# 2V_REG.net
KiCad netlist of a schematic drawn in Altium Designer
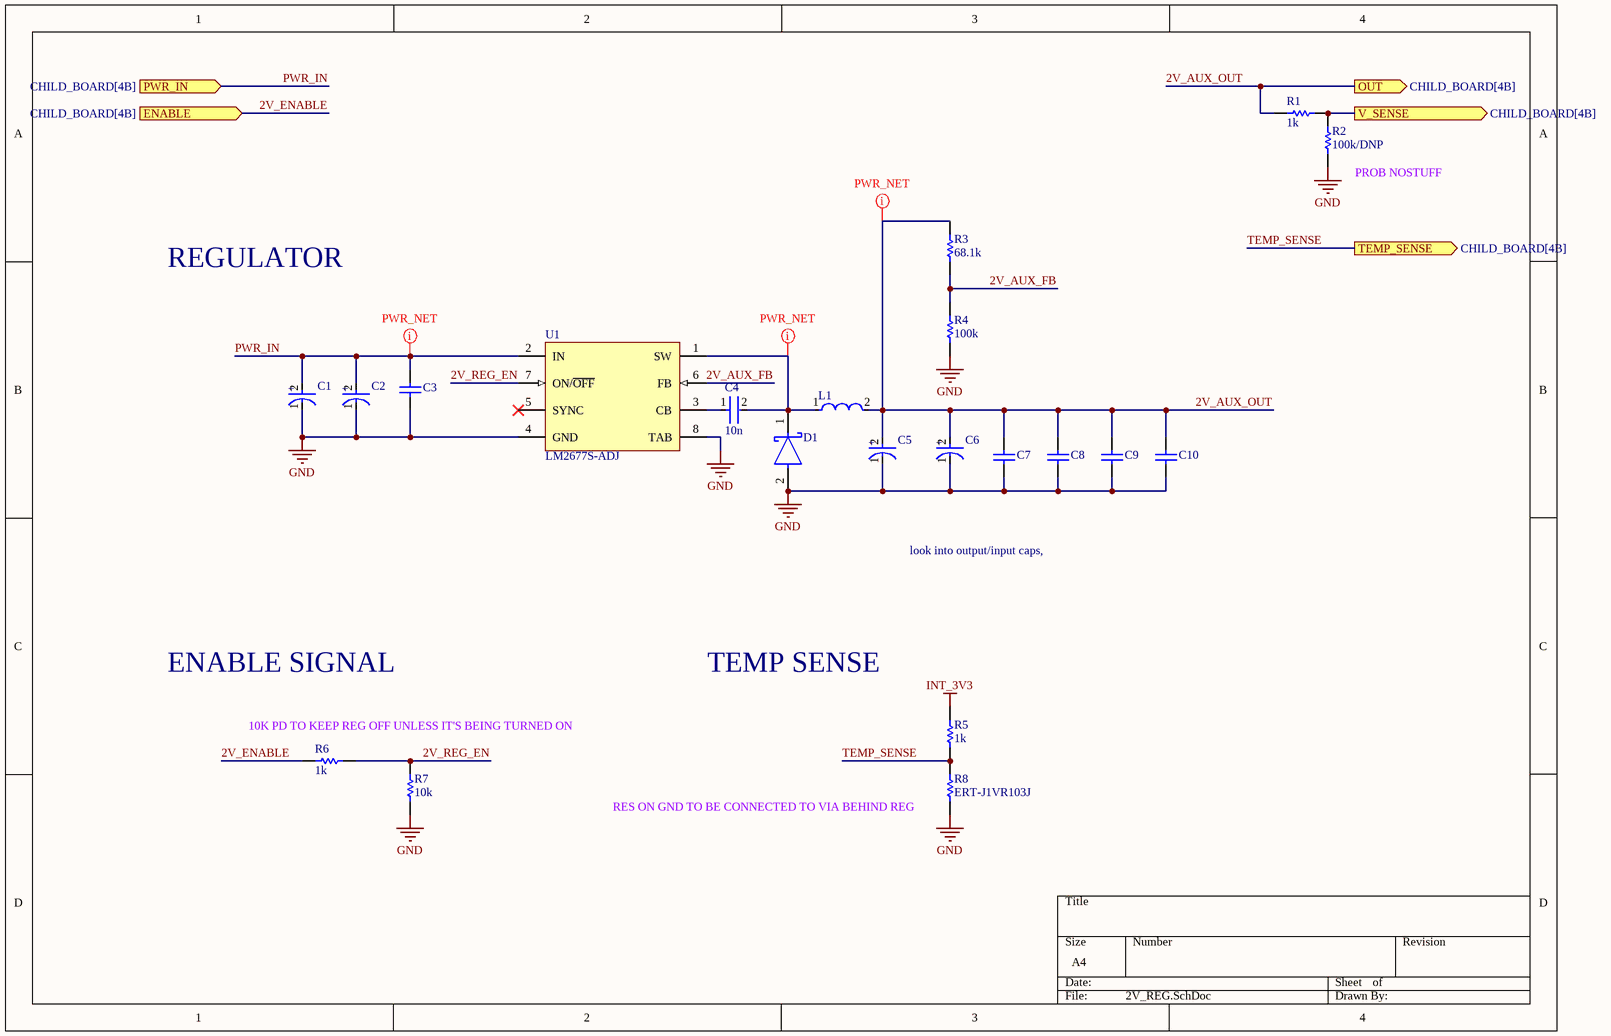
[diagram p0: 2V_REG.SchDoc]

(export (version "E")
  (design (tool "Eeschema 10.0.6"))
  (components
    (comp (ref "C1")
      (value "EEHZA1V680XP")
      (footprint "FP-EEH-D8-MFG")
      (description "Conductive Polymer Hybrid Aluminum Electrolytic Capacitors 68uF ±20% 35V RADIAL SMT 6.3x7.7mm")
      (fields (field (name "VOLTAGE") "35V") (field (name "TOLERANCE") "20%"))
      (libsource (lib "Altium Content Vault") (part "a00bbbee19879c290e62620ae7e47b1"))
    )
    (comp (ref "C2")
      (value "EEHZA1V680XP")
      (footprint "FP-EEH-D8-MFG")
      (description "Conductive Polymer Hybrid Aluminum Electrolytic Capacitors 68uF ±20% 35V RADIAL SMT 6.3x7.7mm")
      (fields (field (name "VOLTAGE") "35V") (field (name "TOLERANCE") "20%"))
      (libsource (lib "Altium Content Vault") (part "a00bbbee19879c290e62620ae7e47b1"))
    )
    (comp (ref "C3")
      (value "CAP 470nF 50V 1812(4532)")
      (footprint "CAPC1812(4532)125_M")
      (description "CAP 470nF 50V ±10% 1812 (4532 Metric) Thickness 1.25mm SMD")
      (fields (field (name "TOLERANCE") "Â±10%"))
      (libsource (lib "Altium Content Vault") (part "CAP"))
    )
    (comp (ref "C4")
      (value "10n")
      (footprint "FP-0402-L_1_0_0_05-W_0_5-IPC_A")
      (description "LARGE PADS, 0402 CAP, CHANGE COMMENT TO MATCH REAL P/N")
      (libsource (lib "Space Concordia") (part "b4654b650e69147ec39a6b967a45e02"))
    )
    (comp (ref "C5")
      (value "16SVPC120M")
      (footprint "FP-OS-CON-SMT-E7-MFG")
      (description "Conductive Polymer Aluminum Solid Capacitors (OS-CON) 120uF ±20% 16V RADIAL SMT 8x6.9mm")
      (fields (field (name "VOLTAGE") "16V") (field (name "TOLERANCE") "20%"))
      (libsource (lib "Altium Content Vault") (part "cf48714ba7e38822c1575c7ec0b6d1f"))
    )
    (comp (ref "C6")
      (value "16SVPC120M")
      (footprint "FP-OS-CON-SMT-E7-MFG")
      (description "Conductive Polymer Aluminum Solid Capacitors (OS-CON) 120uF ±20% 16V RADIAL SMT 8x6.9mm")
      (fields (field (name "VOLTAGE") "16V") (field (name "TOLERANCE") "20%"))
      (libsource (lib "Altium Content Vault") (part "cf48714ba7e38822c1575c7ec0b6d1f"))
    )
    (comp (ref "C7")
      (value "CAP 470nF 50V 1812(4532)")
      (footprint "CAPC1812(4532)125_M")
      (description "CAP 470nF 50V ±10% 1812 (4532 Metric) Thickness 1.25mm SMD")
      (fields (field (name "TOLERANCE") "Â±10%"))
      (libsource (lib "Altium Content Vault") (part "CAP"))
    )
    (comp (ref "C8")
      (value "CAP 470nF 50V 1812(4532)")
      (footprint "CAPC1812(4532)125_M")
      (description "CAP 470nF 50V ±10% 1812 (4532 Metric) Thickness 1.25mm SMD")
      (fields (field (name "TOLERANCE") "Â±10%"))
      (libsource (lib "Altium Content Vault") (part "CAP"))
    )
    (comp (ref "C9")
      (value "CAP 470nF 50V 1812(4532)")
      (footprint "CAPC1812(4532)125_M")
      (description "CAP 470nF 50V ±10% 1812 (4532 Metric) Thickness 1.25mm SMD")
      (fields (field (name "TOLERANCE") "Â±10%"))
      (libsource (lib "Altium Content Vault") (part "CAP"))
    )
    (comp (ref "C10")
      (value "CAP 470nF 50V 1812(4532)")
      (footprint "CAPC1812(4532)125_M")
      (description "CAP 470nF 50V ±10% 1812 (4532 Metric) Thickness 1.25mm SMD")
      (fields (field (name "TOLERANCE") "Â±10%"))
      (libsource (lib "Altium Content Vault") (part "CAP"))
    )
    (comp (ref "D1")
      (value "B540C-13-F")
      (footprint "FP-SMC-MFG")
      (description "DIODE SCHOTTKY 40V 5A SMC")
      (fields
        (field (name "OCTOPART") "https://octopart.com/b540c-13-f-diodes+inc.-325873")
        (field (name "MANUFACTURER") "Diodes Inc.")
      )
      (libsource (lib "Altium Content Vault") (part "1d6ec82d83fb6aee721767c19dac4b9"))
    )
    (comp (ref "L1")
      (value "SRR1260-150M")
      (footprint "FP-SRR1260-MFG")
      (description "FIXED IND 15UH 5A 27 MOHM SMD")
      (fields (field (name "TOLERANCE") "20%"))
      (libsource (lib "Altium Content Vault") (part "725321dda6339637d4d059423bc1c3c"))
    )
    (comp (ref "R1")
      (value "1k")
      (footprint "R0603B")
      (description "Resistor")
      (libsource (lib "Space Concordia") (part "Resistor"))
    )
    (comp (ref "R2")
      (value "100k/DNP")
      (footprint "R0603B")
      (description "Resistor")
      (libsource (lib "Space Concordia") (part "Resistor"))
    )
    (comp (ref "R3")
      (value "68.1k")
      (footprint "R0603B")
      (description "Resistor")
      (libsource (lib "Space Concordia") (part "Resistor"))
    )
    (comp (ref "R4")
      (value "100k")
      (footprint "R0603B")
      (description "Resistor")
      (libsource (lib "Space Concordia") (part "Resistor"))
    )
    (comp (ref "R5")
      (value "1k")
      (footprint "R0603B")
      (description "Resistor")
      (libsource (lib "Space Concordia") (part "Resistor"))
    )
    (comp (ref "R6")
      (value "1k")
      (footprint "R0603B")
      (description "Resistor")
      (libsource (lib "Space Concordia") (part "Resistor"))
    )
    (comp (ref "R7")
      (value "10k")
      (footprint "R0603B")
      (description "Resistor")
      (libsource (lib "Space Concordia") (part "Resistor"))
    )
    (comp (ref "R8")
      (value "ERT-J1VR103J")
      (footprint "RESC1608X90X30ML15T20")
      (fields (field (name "MANUFACTURER") "Panasonic"))
      (libsource (lib "Altium Content Vault") (part "RES"))
    )
    (comp (ref "U1")
      (value "LM2677S-ADJ")
      (footprint "KTW0007B_M")
      (description "SIMPLE SWITCHER® High Efficiency 5A Step-Down Voltage Regulator with Sync, 7-pin TO-263")
      (fields (field (name "MANUFACTURER") "Texas Instruments"))
      (libsource (lib "Altium Content Vault") (part "PM-REG-LM2670S-12"))
    )
  )
  (nets
    (net (code "1") (name "/2V_AUX_FB") (class "Default")
      (node (ref "R3") (pin "2") (pinfunction "2_2") (pintype "passive"))
      (node (ref "R4") (pin "1") (pinfunction "1_1") (pintype "passive"))
      (node (ref "U1") (pin "6") (pinfunction "FB_6") (pintype "input"))
    )
    (net (code "2") (name "/2V_AUX_OUT") (class "Default")
      (node (ref "C10") (pin "2") (pinfunction "2_2") (pintype "passive"))
      (node (ref "C5") (pin "2") (pinfunction "A_2") (pintype "passive"))
      (node (ref "C6") (pin "2") (pinfunction "A_2") (pintype "passive"))
      (node (ref "C7") (pin "2") (pinfunction "2_2") (pintype "passive"))
      (node (ref "C8") (pin "2") (pinfunction "2_2") (pintype "passive"))
      (node (ref "C9") (pin "2") (pinfunction "2_2") (pintype "passive"))
      (node (ref "L1") (pin "2") (pinfunction "2_2") (pintype "passive"))
      (node (ref "R1") (pin "1") (pinfunction "1_1") (pintype "passive"))
      (node (ref "R3") (pin "1") (pinfunction "1_1") (pintype "passive"))
    )
    (net (code "3") (name "/2V_ENABLE") (class "Default")
      (node (ref "R6") (pin "1") (pinfunction "1_1") (pintype "passive"))
    )
    (net (code "4") (name "/2V_REG_EN") (class "Default")
      (node (ref "R6") (pin "2") (pinfunction "2_2") (pintype "passive"))
      (node (ref "R7") (pin "1") (pinfunction "1_1") (pintype "passive"))
      (node (ref "U1") (pin "7") (pinfunction "ON/~{OFF}_7") (pintype "input"))
    )
    (net (code "5") (name "/PWR_IN") (class "Default")
      (node (ref "C1") (pin "2") (pinfunction "A_2") (pintype "passive"))
      (node (ref "C2") (pin "2") (pinfunction "A_2") (pintype "passive"))
      (node (ref "C3") (pin "2") (pinfunction "2_2") (pintype "passive"))
      (node (ref "U1") (pin "2") (pinfunction "IN_2") (pintype "power_in"))
    )
    (net (code "6") (name "/TEMP_SENSE") (class "Default")
      (node (ref "R5") (pin "1") (pinfunction "1_1") (pintype "passive"))
      (node (ref "R8") (pin "2") (pinfunction "2_2") (pintype "passive"))
    )
    (net (code "7") (name "/V_SENSE") (class "Default")
      (node (ref "R1") (pin "2") (pinfunction "2_2") (pintype "passive"))
      (node (ref "R2") (pin "1") (pinfunction "1_1") (pintype "passive"))
    )
    (net (code "8") (name "GND") (class "Default")
      (node (ref "C1") (pin "1") (pinfunction "C_1") (pintype "passive"))
      (node (ref "C10") (pin "1") (pinfunction "1_1") (pintype "passive"))
      (node (ref "C2") (pin "1") (pinfunction "C_1") (pintype "passive"))
      (node (ref "C3") (pin "1") (pinfunction "1_1") (pintype "passive"))
      (node (ref "C5") (pin "1") (pinfunction "C_1") (pintype "passive"))
      (node (ref "C6") (pin "1") (pinfunction "C_1") (pintype "passive"))
      (node (ref "C7") (pin "1") (pinfunction "1_1") (pintype "passive"))
      (node (ref "C8") (pin "1") (pinfunction "1_1") (pintype "passive"))
      (node (ref "C9") (pin "1") (pinfunction "1_1") (pintype "passive"))
      (node (ref "D1") (pin "2") (pinfunction "A_2") (pintype "passive"))
      (node (ref "R2") (pin "2") (pinfunction "2_2") (pintype "passive"))
      (node (ref "R4") (pin "2") (pinfunction "2_2") (pintype "passive"))
      (node (ref "R7") (pin "2") (pinfunction "2_2") (pintype "passive"))
      (node (ref "R8") (pin "1") (pinfunction "1_1") (pintype "passive"))
      (node (ref "U1") (pin "4") (pinfunction "GND_4") (pintype "power_in"))
      (node (ref "U1") (pin "8") (pinfunction "TAB_8") (pintype "passive"))
    )
    (net (code "9") (name "INT_3V3") (class "Default")
      (node (ref "R5") (pin "2") (pinfunction "2_2") (pintype "passive"))
    )
    (net (code "10") (name "Net-(D1-C)") (class "Default")
      (node (ref "C4") (pin "2") (pinfunction "2_2") (pintype "passive"))
      (node (ref "D1") (pin "1") (pinfunction "C_1") (pintype "passive"))
      (node (ref "L1") (pin "1") (pinfunction "1_1") (pintype "passive"))
      (node (ref "U1") (pin "1") (pinfunction "SW_1") (pintype "power_in"))
    )
    (net (code "11") (name "Net-(U1-CB)") (class "Default")
      (node (ref "C4") (pin "1") (pinfunction "1_1") (pintype "passive"))
      (node (ref "U1") (pin "3") (pinfunction "CB_3") (pintype "passive"))
    )
    (net (code "12") (name "unconnected-(U1-SYNC-Pad5)") (class "Default")
      (node (ref "U1") (pin "5") (pinfunction "SYNC_5") (pintype "passive+no_connect"))
    )
  )
)
